# SCH_Hacker-NFC_2024-06-30.net
KiCad netlist of a schematic drawn in EasyEDA
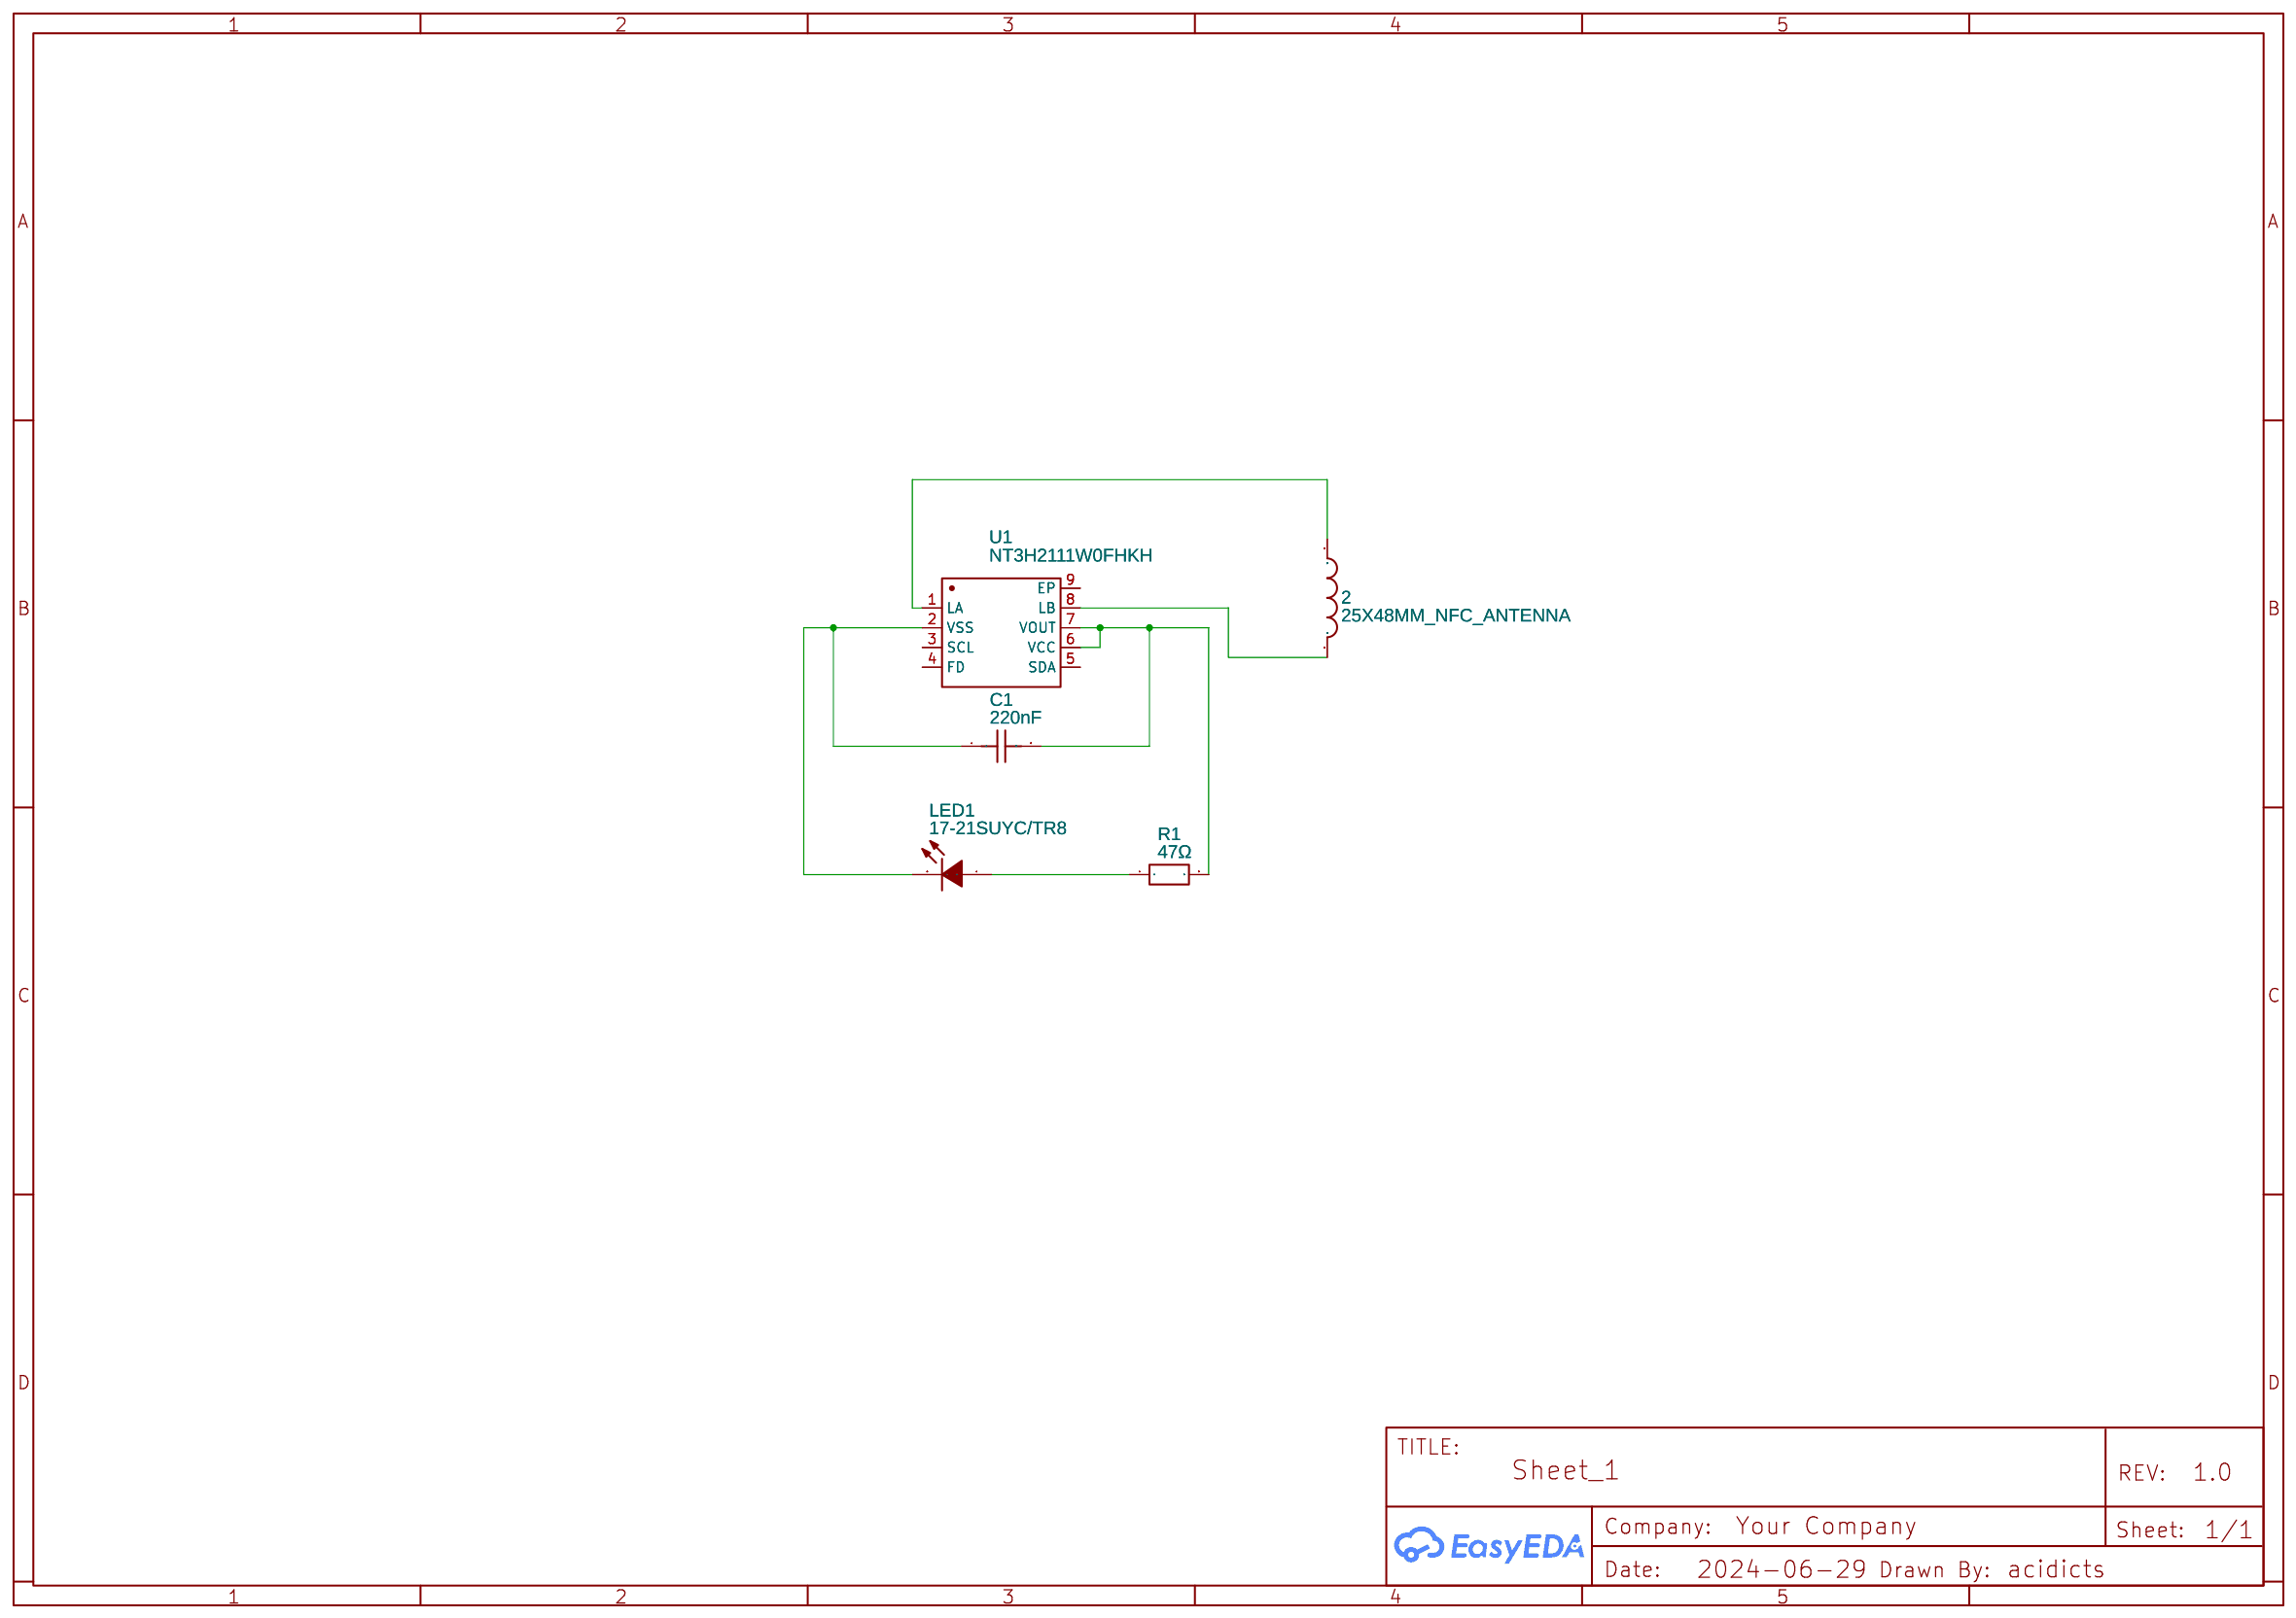
[diagram p0: schematic sheet]

(export (version "E")
  (design (tool "Eeschema 10.0.6"))
  (components
    (comp (ref "2") (value "25X48MM_NFC_ANTENNA") (libsource (lib "") (part "25X48MM_NFC_ANTENNA")))
    (comp (ref "C1") (value "220nF") (libsource (lib "") (part "C_0603_US")))
    (comp (ref "LED1")
      (value "17-21SUYC/TR8")
      (fields (field (name "Manufacturer Part") "KT-0805黄灯") (field (name "Manufacturer") "KENTO"))
      (libsource (lib "") (part "17-21SUYC/TR8"))
    )
    (comp (ref "R1") (value "47Ω") (libsource (lib "") (part "R_0603_EU")))
    (comp (ref "U1")
      (value "NT3H2111W0FHKH")
      (fields (field (name "Manufacturer") "NXP(恩智浦)"))
      (libsource (lib "") (part "NT3H2111W0FHKH"))
    )
  )
  (nets
    (net (code "1") (name "Net-(LED1-+)") (class "Default")
      (node (ref "LED1") (pin "1") (pinfunction "+_1") (pintype "unspecified"))
      (node (ref "R1") (pin "1") (pinfunction "1_1") (pintype "unspecified"))
    )
    (net (code "2") (name "Net-(LED1--)") (class "Default")
      (node (ref "C1") (pin "1") (pinfunction "1_1") (pintype "unspecified"))
      (node (ref "LED1") (pin "2") (pinfunction "-_2") (pintype "unspecified"))
      (node (ref "U1") (pin "2") (pinfunction "VSS_2") (pintype "unspecified"))
    )
    (net (code "3") (name "Net-(U1-LA)") (class "Default")
      (node (ref "2") (pin "P$1") (pinfunction "P$1_P$1") (pintype "bidirectional"))
      (node (ref "U1") (pin "1") (pinfunction "LA_1") (pintype "unspecified"))
    )
    (net (code "4") (name "Net-(U1-LB)") (class "Default")
      (node (ref "2") (pin "P$2") (pinfunction "P$2_P$2") (pintype "bidirectional"))
      (node (ref "U1") (pin "8") (pinfunction "LB_8") (pintype "unspecified"))
    )
    (net (code "5") (name "Net-(U1-VCC)") (class "Default")
      (node (ref "C1") (pin "2") (pinfunction "2_2") (pintype "unspecified"))
      (node (ref "R1") (pin "2") (pinfunction "2_2") (pintype "unspecified"))
      (node (ref "U1") (pin "6") (pinfunction "VCC_6") (pintype "unspecified"))
      (node (ref "U1") (pin "7") (pinfunction "VOUT_7") (pintype "unspecified"))
    )
    (net (code "6") (name "unconnected-(U1-EP-Pad9)") (class "Default")
      (node (ref "U1") (pin "9") (pinfunction "EP_9") (pintype "unspecified"))
    )
    (net (code "7") (name "unconnected-(U1-FD-Pad4)") (class "Default")
      (node (ref "U1") (pin "4") (pinfunction "FD_4") (pintype "unspecified"))
    )
    (net (code "8") (name "unconnected-(U1-SCL-Pad3)") (class "Default")
      (node (ref "U1") (pin "3") (pinfunction "SCL_3") (pintype "unspecified"))
    )
    (net (code "9") (name "unconnected-(U1-SDA-Pad5)") (class "Default")
      (node (ref "U1") (pin "5") (pinfunction "SDA_5") (pintype "unspecified"))
    )
  )
)
